# schematics.net
KiCad netlist of a schematic drawn in EAGLE
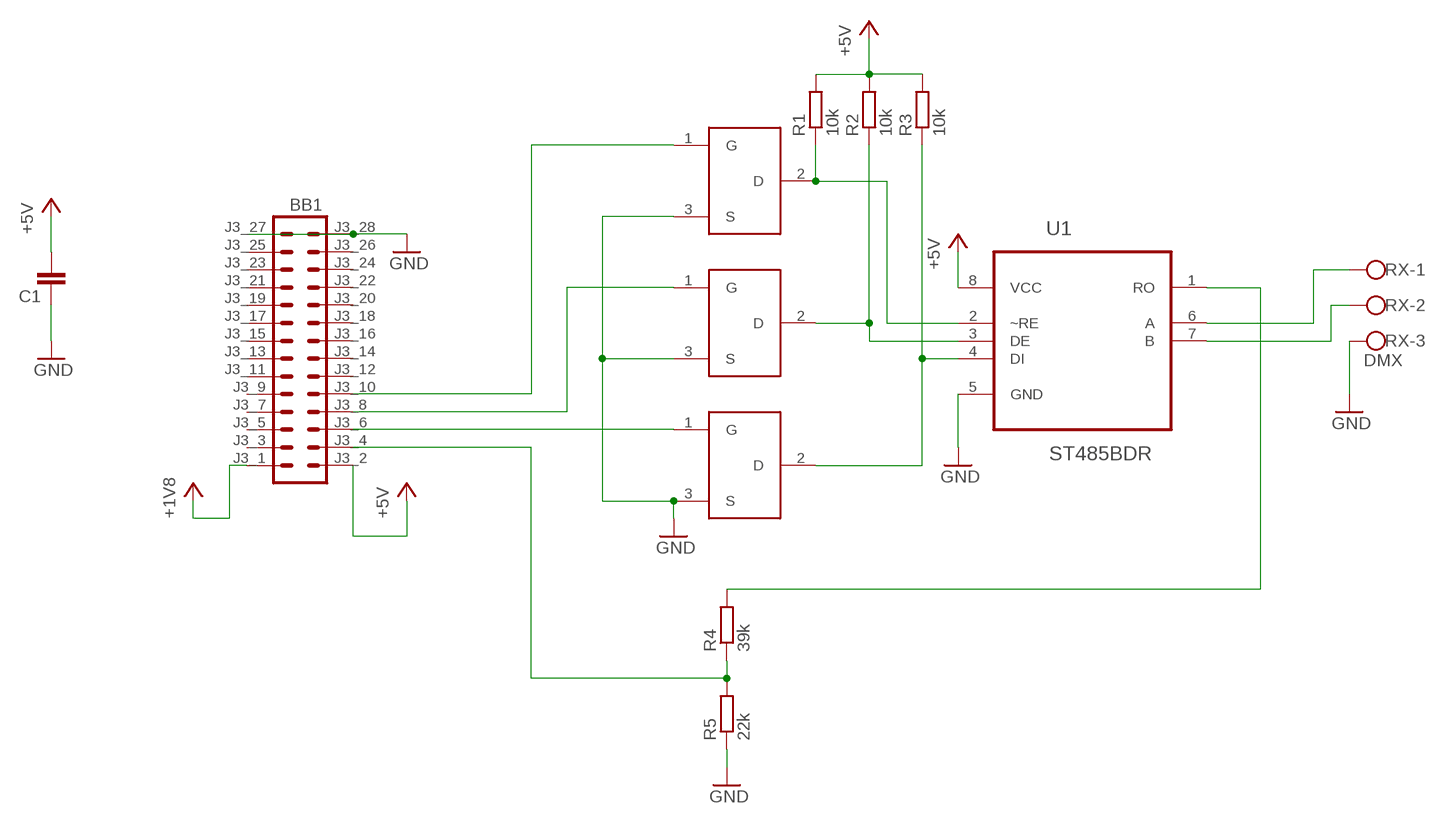
[diagram p0: schematic, sheet 1]

(export (version "E")
  (design (tool "Eeschema 10.0.6"))
  (components
    (comp (ref "BB1")
      (value "BEAGLE_EXPANSION")
      (footprint "eagle-import:BEAGLE_EXPANSION")
      (libsource (lib "eagle-import") (part "BEAGLE_EXPANSION"))
    )
    (comp (ref "C1")
      (value "C-EUC0603")
      (footprint "eagle-import:C0603")
      (libsource (lib "eagle-import") (part "C-EUC0603"))
    )
    (comp (ref "R1")
      (value "10k")
      (footprint "eagle-import:R0603")
      (libsource (lib "eagle-import") (part "R-EU_R0603"))
    )
    (comp (ref "R2")
      (value "10k")
      (footprint "eagle-import:R0603")
      (libsource (lib "eagle-import") (part "R-EU_R0603"))
    )
    (comp (ref "R3")
      (value "10k")
      (footprint "eagle-import:R0603")
      (libsource (lib "eagle-import") (part "R-EU_R0603"))
    )
    (comp (ref "R4")
      (value "39k")
      (footprint "eagle-import:R0603")
      (libsource (lib "eagle-import") (part "R-EU_R0603"))
    )
    (comp (ref "R5")
      (value "22k")
      (footprint "eagle-import:R0603")
      (libsource (lib "eagle-import") (part "R-EU_R0603"))
    )
    (comp (ref "RX")
      (value "DMX")
      (footprint "eagle-import:W237-103")
      (fields (field (name "MPN") "237-103"))
      (libsource (lib "eagle-import") (part "W237-103"))
    )
    (comp (ref "U$1")
      (value "SI1012CR-T1-GE3")
      (footprint "eagle-import:SC75")
      (libsource (lib "eagle-import") (part "SI1012CR-T1-GE3"))
    )
    (comp (ref "U$2")
      (value "SI1012CR-T1-GE3")
      (footprint "eagle-import:SC75")
      (libsource (lib "eagle-import") (part "SI1012CR-T1-GE3"))
    )
    (comp (ref "U$3")
      (value "SI1012CR-T1-GE3")
      (footprint "eagle-import:SC75")
      (libsource (lib "eagle-import") (part "SI1012CR-T1-GE3"))
    )
    (comp (ref "U1")
      (value "ST485BDR")
      (footprint "eagle-import:SOIC127P600X175-8N")
      (fields (field (name "MF") "STMicroelectronics") (field (name "MP") " ST485BDR "))
      (libsource (lib "eagle-import") (part "ST485BDR"))
    )
  )
  (nets
    (net (code "1") (name "+1V8") (class "Default")
      (node (ref "BB1") (pin "J3_1") (pinfunction "1_J3_1") (pintype "passive"))
    )
    (net (code "2") (name "+5V") (class "Default")
      (node (ref "BB1") (pin "J3_2") (pinfunction "2_J3_2") (pintype "passive"))
      (node (ref "C1") (pin "2") (pinfunction "2_2") (pintype "passive"))
      (node (ref "R1") (pin "2") (pinfunction "2_2") (pintype "passive"))
      (node (ref "R2") (pin "2") (pinfunction "2_2") (pintype "passive"))
      (node (ref "R3") (pin "2") (pinfunction "2_2") (pintype "passive"))
      (node (ref "U1") (pin "8") (pinfunction "VCC_8") (pintype "power_in"))
    )
    (net (code "3") (name "GND") (class "Default")
      (node (ref "BB1") (pin "J3_27") (pinfunction "27_J3_27") (pintype "passive"))
      (node (ref "BB1") (pin "J3_28") (pinfunction "28_J3_28") (pintype "passive"))
      (node (ref "C1") (pin "1") (pinfunction "1_1") (pintype "passive"))
      (node (ref "R5") (pin "1") (pinfunction "1_1") (pintype "passive"))
      (node (ref "RX") (pin "3") (pinfunction "KL_3") (pintype "passive"))
      (node (ref "U$1") (pin "3") (pinfunction "S_3") (pintype "bidirectional"))
      (node (ref "U$2") (pin "3") (pinfunction "S_3") (pintype "bidirectional"))
      (node (ref "U$3") (pin "3") (pinfunction "S_3") (pintype "bidirectional"))
      (node (ref "U1") (pin "5") (pinfunction "GND_5") (pintype "passive"))
    )
    (net (code "4") (name "Net-(BB1-4)") (class "Default")
      (node (ref "BB1") (pin "J3_4") (pinfunction "4_J3_4") (pintype "passive"))
      (node (ref "R4") (pin "1") (pinfunction "1_1") (pintype "passive"))
      (node (ref "R5") (pin "2") (pinfunction "2_2") (pintype "passive"))
    )
    (net (code "5") (name "Net-(BB1-6)") (class "Default")
      (node (ref "BB1") (pin "J3_6") (pinfunction "6_J3_6") (pintype "passive"))
      (node (ref "U$2") (pin "1") (pinfunction "G_1") (pintype "bidirectional"))
    )
    (net (code "6") (name "Net-(BB1-8)") (class "Default")
      (node (ref "BB1") (pin "J3_8") (pinfunction "8_J3_8") (pintype "passive"))
      (node (ref "U$3") (pin "1") (pinfunction "G_1") (pintype "bidirectional"))
    )
    (net (code "7") (name "Net-(BB1-10)") (class "Default")
      (node (ref "BB1") (pin "J3_10") (pinfunction "10_J3_10") (pintype "passive"))
      (node (ref "U$1") (pin "1") (pinfunction "G_1") (pintype "bidirectional"))
    )
    (net (code "8") (name "Net-(RXA-KL)") (class "Default")
      (node (ref "RX") (pin "1") (pinfunction "KL_1") (pintype "passive"))
      (node (ref "U1") (pin "6") (pinfunction "A_6") (pintype "bidirectional"))
    )
    (net (code "9") (name "Net-(RXB-KL)") (class "Default")
      (node (ref "RX") (pin "2") (pinfunction "KL_2") (pintype "passive"))
      (node (ref "U1") (pin "7") (pinfunction "B_7") (pintype "bidirectional"))
    )
    (net (code "10") (name "Net-(U$1-D)") (class "Default")
      (node (ref "R1") (pin "1") (pinfunction "1_1") (pintype "passive"))
      (node (ref "U$1") (pin "2") (pinfunction "D_2") (pintype "bidirectional"))
      (node (ref "U1") (pin "2") (pinfunction "~{RE}_2") (pintype "input"))
    )
    (net (code "11") (name "Net-(U$2-D)") (class "Default")
      (node (ref "R3") (pin "1") (pinfunction "1_1") (pintype "passive"))
      (node (ref "U$2") (pin "2") (pinfunction "D_2") (pintype "bidirectional"))
      (node (ref "U1") (pin "4") (pinfunction "DI_4") (pintype "input"))
    )
    (net (code "12") (name "Net-(U$3-D)") (class "Default")
      (node (ref "R2") (pin "1") (pinfunction "1_1") (pintype "passive"))
      (node (ref "U$3") (pin "2") (pinfunction "D_2") (pintype "bidirectional"))
      (node (ref "U1") (pin "3") (pinfunction "DE_3") (pintype "input"))
    )
    (net (code "13") (name "Net-(U1-RO)") (class "Default")
      (node (ref "R4") (pin "2") (pinfunction "2_2") (pintype "passive"))
      (node (ref "U1") (pin "1") (pinfunction "RO_1") (pintype "output"))
    )
    (net (code "14") (name "unconnected-(BB1-3-PadJ3_3)") (class "Default")
      (node (ref "BB1") (pin "J3_3") (pinfunction "3_J3_3") (pintype "passive"))
    )
    (net (code "15") (name "unconnected-(BB1-5-PadJ3_5)") (class "Default")
      (node (ref "BB1") (pin "J3_5") (pinfunction "5_J3_5") (pintype "passive"))
    )
    (net (code "16") (name "unconnected-(BB1-7-PadJ3_7)") (class "Default")
      (node (ref "BB1") (pin "J3_7") (pinfunction "7_J3_7") (pintype "passive"))
    )
    (net (code "17") (name "unconnected-(BB1-9-PadJ3_9)") (class "Default")
      (node (ref "BB1") (pin "J3_9") (pinfunction "9_J3_9") (pintype "passive"))
    )
    (net (code "18") (name "unconnected-(BB1-11-PadJ3_11)") (class "Default")
      (node (ref "BB1") (pin "J3_11") (pinfunction "11_J3_11") (pintype "passive"))
    )
    (net (code "19") (name "unconnected-(BB1-12-PadJ3_12)") (class "Default")
      (node (ref "BB1") (pin "J3_12") (pinfunction "12_J3_12") (pintype "passive"))
    )
    (net (code "20") (name "unconnected-(BB1-13-PadJ3_13)") (class "Default")
      (node (ref "BB1") (pin "J3_13") (pinfunction "13_J3_13") (pintype "passive"))
    )
    (net (code "21") (name "unconnected-(BB1-14-PadJ3_14)") (class "Default")
      (node (ref "BB1") (pin "J3_14") (pinfunction "14_J3_14") (pintype "passive"))
    )
    (net (code "22") (name "unconnected-(BB1-15-PadJ3_15)") (class "Default")
      (node (ref "BB1") (pin "J3_15") (pinfunction "15_J3_15") (pintype "passive"))
    )
    (net (code "23") (name "unconnected-(BB1-16-PadJ3_16)") (class "Default")
      (node (ref "BB1") (pin "J3_16") (pinfunction "16_J3_16") (pintype "passive"))
    )
    (net (code "24") (name "unconnected-(BB1-17-PadJ3_17)") (class "Default")
      (node (ref "BB1") (pin "J3_17") (pinfunction "17_J3_17") (pintype "passive"))
    )
    (net (code "25") (name "unconnected-(BB1-18-PadJ3_18)") (class "Default")
      (node (ref "BB1") (pin "J3_18") (pinfunction "18_J3_18") (pintype "passive"))
    )
    (net (code "26") (name "unconnected-(BB1-19-PadJ3_19)") (class "Default")
      (node (ref "BB1") (pin "J3_19") (pinfunction "19_J3_19") (pintype "passive"))
    )
    (net (code "27") (name "unconnected-(BB1-20-PadJ3_20)") (class "Default")
      (node (ref "BB1") (pin "J3_20") (pinfunction "20_J3_20") (pintype "passive"))
    )
    (net (code "28") (name "unconnected-(BB1-21-PadJ3_21)") (class "Default")
      (node (ref "BB1") (pin "J3_21") (pinfunction "21_J3_21") (pintype "passive"))
    )
    (net (code "29") (name "unconnected-(BB1-22-PadJ3_22)") (class "Default")
      (node (ref "BB1") (pin "J3_22") (pinfunction "22_J3_22") (pintype "passive"))
    )
    (net (code "30") (name "unconnected-(BB1-23-PadJ3_23)") (class "Default")
      (node (ref "BB1") (pin "J3_23") (pinfunction "23_J3_23") (pintype "passive"))
    )
    (net (code "31") (name "unconnected-(BB1-24-PadJ3_24)") (class "Default")
      (node (ref "BB1") (pin "J3_24") (pinfunction "24_J3_24") (pintype "passive"))
    )
    (net (code "32") (name "unconnected-(BB1-25-PadJ3_25)") (class "Default")
      (node (ref "BB1") (pin "J3_25") (pinfunction "25_J3_25") (pintype "passive"))
    )
    (net (code "33") (name "unconnected-(BB1-26-PadJ3_26)") (class "Default")
      (node (ref "BB1") (pin "J3_26") (pinfunction "26_J3_26") (pintype "passive"))
    )
  )
)
